# TOP.net
KiCad netlist of a schematic drawn in Altium Designer
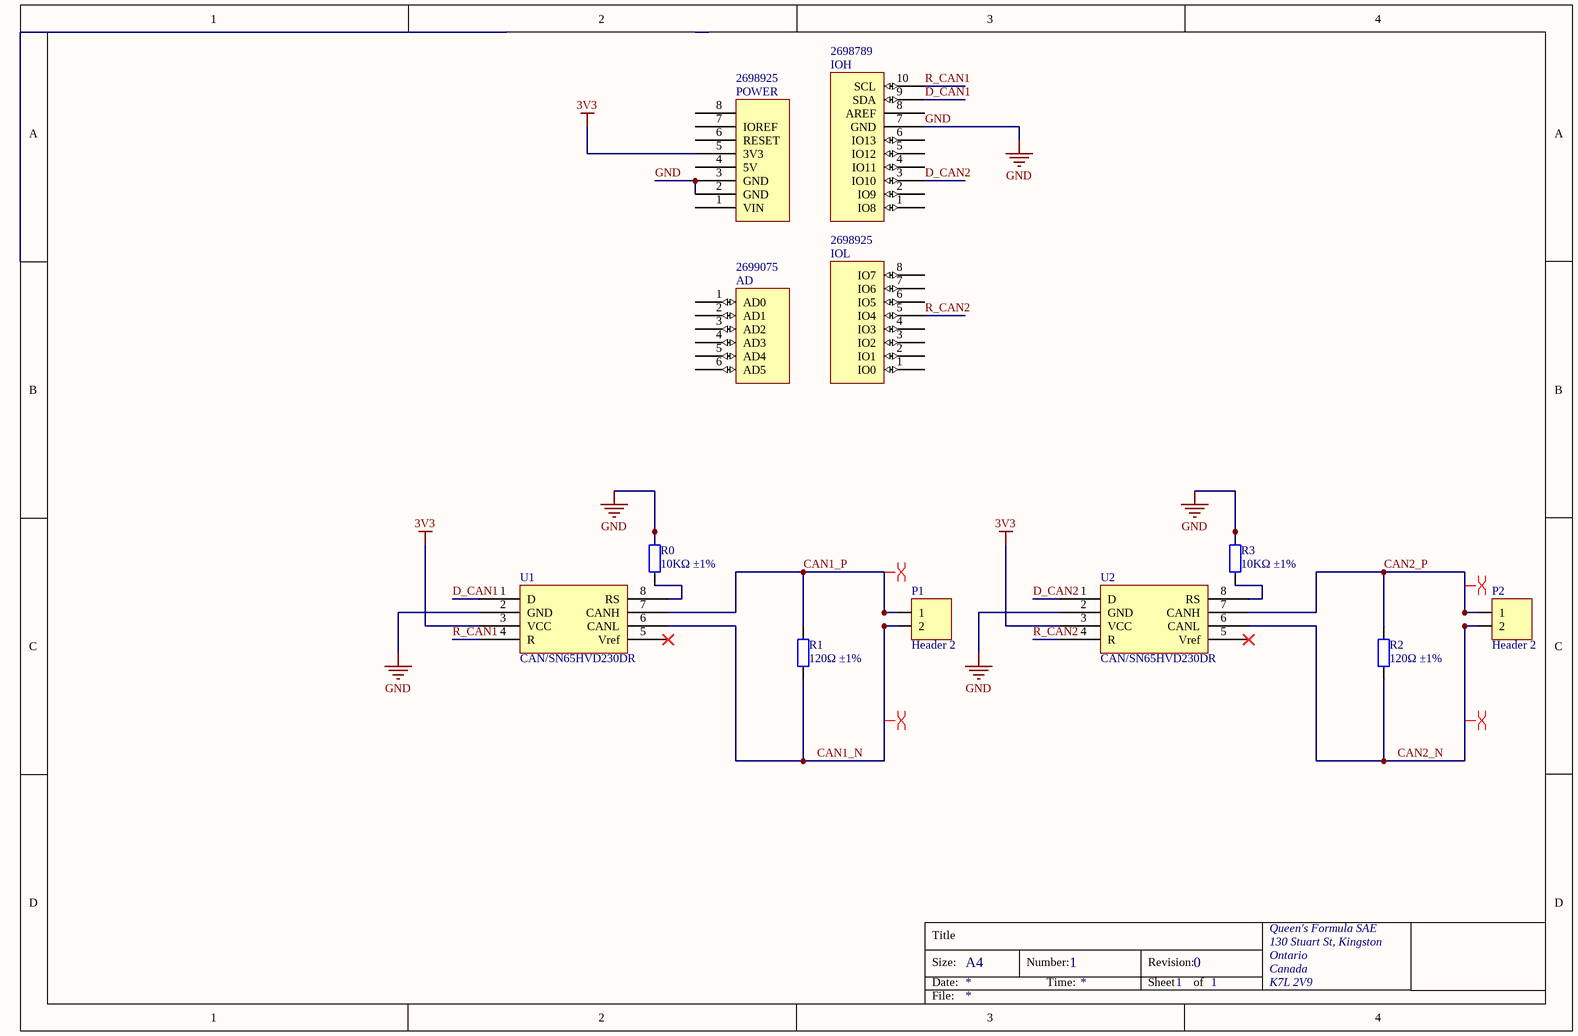
[diagram p0: TOP.SchDoc]

(export (version "E")
  (design (tool "Eeschema 10.0.6"))
  (components
    (comp (ref "AD")
      (value "AD")
      (footprint "Header:Header 6x1 8.5mm")
      (fields (field (name "SUPPLIER PART NUMBER 4") "2699075"))
      (libsource (lib "Header") (part "AD"))
    )
    (comp (ref "IOH")
      (value "IOH")
      (footprint "Header:Header 10x1 8.5mm")
      (fields (field (name "SUPPLIER PART NUMBER 3") "2698789"))
      (libsource (lib "Header") (part "IOH"))
    )
    (comp (ref "IOL")
      (value "IOL")
      (footprint "Header 8x1 8.5mm")
      (fields (field (name "SUPPLIER PART NUMBER 4") "2698925"))
      (libsource (lib "Header") (part "IOL"))
    )
    (comp (ref "P1")
      (value "Header 2")
      (footprint "HDR1X2")
      (description "Header, 2-Pin")
      (fields (field (name "PUBLISHER") "Altium Limited"))
      (libsource (lib "Miscellaneous Connectors") (part "Header 2"))
    )
    (comp (ref "P2")
      (value "Header 2")
      (footprint "HDR1X2")
      (description "Header, 2-Pin")
      (fields (field (name "PUBLISHER") "Altium Limited"))
      (libsource (lib "Miscellaneous Connectors") (part "Header 2"))
    )
    (comp (ref "POWER")
      (value "POWER_UNO")
      (footprint "Header 8x1 8.5mm")
      (fields (field (name "SUPPLIER PART NUMBER 4") "2698925"))
      (libsource (lib "Header") (part "POWER_UNO"))
    )
    (comp (ref "R0")
      (value "10KΩ ±1%")
      (footprint "0402_R")
      (description "Chip resistor")
      (fields (field (name "MANUFACTURER") "Uniroyal Elec") (field (name "PARTNUMBER") "0402WGF1002TCE"))
      (libsource (lib "RES") (part "0402 10K (1002) 1%"))
    )
    (comp (ref "R1")
      (value "120Ω ±1%")
      (footprint "0805_R")
      (description "Chip resistor")
      (fields (field (name "MANUFACTURER") "Uniroyal Elec") (field (name "POWER") "1/8W"))
      (libsource (lib "RES") (part "0805 120R (1200) 1%"))
    )
    (comp (ref "R2")
      (value "120Ω ±1%")
      (footprint "0805_R")
      (description "Chip resistor")
      (fields (field (name "MANUFACTURER") "Uniroyal Elec") (field (name "POWER") "1/8W"))
      (libsource (lib "RES") (part "0805 120R (1200) 1%"))
    )
    (comp (ref "R3")
      (value "10KΩ ±1%")
      (footprint "0402_R")
      (description "Chip resistor")
      (fields (field (name "MANUFACTURER") "Uniroyal Elec") (field (name "PARTNUMBER") "0402WGF1002TCE"))
      (libsource (lib "RES") (part "0402 10K (1002) 1%"))
    )
    (comp (ref "U1")
      (value "CAN/SN65HVD230DR")
      (footprint "SOIC-8_150mil")
      (description "CAN")
      (libsource (lib "IC") (part "CAN/SN65HVD230DR_[C12084]"))
    )
    (comp (ref "U2")
      (value "CAN/SN65HVD230DR")
      (footprint "SOIC-8_150mil")
      (description "CAN")
      (libsource (lib "IC") (part "CAN/SN65HVD230DR_[C12084]"))
    )
  )
  (nets
    (net (code "1") (name "/CAN1_N") (class "Default")
      (node (ref "P1") (pin "2") (pinfunction "2_2") (pintype "passive"))
      (node (ref "R1") (pin "2") (pinfunction "2_2") (pintype "passive"))
      (node (ref "U1") (pin "6") (pinfunction "CANL_6") (pintype "passive"))
    )
    (net (code "2") (name "/CAN1_P") (class "Default")
      (node (ref "P1") (pin "1") (pinfunction "1_1") (pintype "passive"))
      (node (ref "R1") (pin "1") (pinfunction "1_1") (pintype "passive"))
      (node (ref "U1") (pin "7") (pinfunction "CANH_7") (pintype "passive"))
    )
    (net (code "3") (name "/CAN2_N") (class "Default")
      (node (ref "P2") (pin "2") (pinfunction "2_2") (pintype "passive"))
      (node (ref "R2") (pin "2") (pinfunction "2_2") (pintype "passive"))
      (node (ref "U2") (pin "6") (pinfunction "CANL_6") (pintype "passive"))
    )
    (net (code "4") (name "/CAN2_P") (class "Default")
      (node (ref "P2") (pin "1") (pinfunction "1_1") (pintype "passive"))
      (node (ref "R2") (pin "1") (pinfunction "1_1") (pintype "passive"))
      (node (ref "U2") (pin "7") (pinfunction "CANH_7") (pintype "passive"))
    )
    (net (code "5") (name "/D_CAN1") (class "Default")
      (node (ref "IOH") (pin "9") (pinfunction "SDA_9") (pintype "bidirectional"))
      (node (ref "U1") (pin "1") (pinfunction "D_1") (pintype "passive"))
    )
    (net (code "6") (name "/D_CAN2") (class "Default")
      (node (ref "IOH") (pin "3") (pinfunction "IO10_3") (pintype "bidirectional"))
      (node (ref "U2") (pin "1") (pinfunction "D_1") (pintype "passive"))
    )
    (net (code "7") (name "/R_CAN1") (class "Default")
      (node (ref "IOH") (pin "10") (pinfunction "SCL_10") (pintype "bidirectional"))
      (node (ref "U1") (pin "4") (pinfunction "R_4") (pintype "passive"))
    )
    (net (code "8") (name "/R_CAN2") (class "Default")
      (node (ref "IOL") (pin "5") (pinfunction "IO4_5") (pintype "bidirectional"))
      (node (ref "U2") (pin "4") (pinfunction "R_4") (pintype "passive"))
    )
    (net (code "9") (name "3V3") (class "Default")
      (node (ref "POWER") (pin "5") (pinfunction "3V3_5") (pintype "power_in"))
      (node (ref "U1") (pin "3") (pinfunction "VCC_3") (pintype "passive"))
      (node (ref "U2") (pin "3") (pinfunction "VCC_3") (pintype "passive"))
    )
    (net (code "10") (name "GND") (class "Default")
      (node (ref "IOH") (pin "7") (pinfunction "GND_7") (pintype "power_in"))
      (node (ref "POWER") (pin "2") (pinfunction "GND_2") (pintype "power_in"))
      (node (ref "POWER") (pin "3") (pinfunction "GND_3") (pintype "power_in"))
      (node (ref "R0") (pin "2") (pinfunction "2_2") (pintype "passive"))
      (node (ref "R3") (pin "2") (pinfunction "2_2") (pintype "passive"))
      (node (ref "U1") (pin "2") (pinfunction "GND_2") (pintype "passive"))
      (node (ref "U2") (pin "2") (pinfunction "GND_2") (pintype "passive"))
    )
    (net (code "11") (name "Net-(U1-RS)") (class "Default")
      (node (ref "R0") (pin "1") (pinfunction "1_1") (pintype "passive"))
      (node (ref "U1") (pin "8") (pinfunction "RS_8") (pintype "passive"))
    )
    (net (code "12") (name "Net-(U2-RS)") (class "Default")
      (node (ref "R3") (pin "1") (pinfunction "1_1") (pintype "passive"))
      (node (ref "U2") (pin "8") (pinfunction "RS_8") (pintype "passive"))
    )
    (net (code "13") (name "unconnected-(AD-AD0-Pad1)") (class "Default")
      (node (ref "AD") (pin "1") (pinfunction "AD0_1") (pintype "bidirectional"))
    )
    (net (code "14") (name "unconnected-(AD-AD1-Pad2)") (class "Default")
      (node (ref "AD") (pin "2") (pinfunction "AD1_2") (pintype "bidirectional"))
    )
    (net (code "15") (name "unconnected-(AD-AD2-Pad3)") (class "Default")
      (node (ref "AD") (pin "3") (pinfunction "AD2_3") (pintype "bidirectional"))
    )
    (net (code "16") (name "unconnected-(AD-AD3-Pad4)") (class "Default")
      (node (ref "AD") (pin "4") (pinfunction "AD3_4") (pintype "bidirectional"))
    )
    (net (code "17") (name "unconnected-(AD-AD4-Pad5)") (class "Default")
      (node (ref "AD") (pin "5") (pinfunction "AD4_5") (pintype "bidirectional"))
    )
    (net (code "18") (name "unconnected-(AD-AD5-Pad6)") (class "Default")
      (node (ref "AD") (pin "6") (pinfunction "AD5_6") (pintype "bidirectional"))
    )
    (net (code "19") (name "unconnected-(IOH-AREF-Pad8)") (class "Default")
      (node (ref "IOH") (pin "8") (pinfunction "AREF_8") (pintype "passive"))
    )
    (net (code "20") (name "unconnected-(IOH-IO8-Pad1)") (class "Default")
      (node (ref "IOH") (pin "1") (pinfunction "IO8_1") (pintype "bidirectional"))
    )
    (net (code "21") (name "unconnected-(IOH-IO9-Pad2)") (class "Default")
      (node (ref "IOH") (pin "2") (pinfunction "IO9_2") (pintype "bidirectional"))
    )
    (net (code "22") (name "unconnected-(IOH-IO11-Pad4)") (class "Default")
      (node (ref "IOH") (pin "4") (pinfunction "IO11_4") (pintype "bidirectional"))
    )
    (net (code "23") (name "unconnected-(IOH-IO12-Pad5)") (class "Default")
      (node (ref "IOH") (pin "5") (pinfunction "IO12_5") (pintype "bidirectional"))
    )
    (net (code "24") (name "unconnected-(IOH-IO13-Pad6)") (class "Default")
      (node (ref "IOH") (pin "6") (pinfunction "IO13_6") (pintype "bidirectional"))
    )
    (net (code "25") (name "unconnected-(IOL-IO0-Pad1)") (class "Default")
      (node (ref "IOL") (pin "1") (pinfunction "IO0_1") (pintype "bidirectional"))
    )
    (net (code "26") (name "unconnected-(IOL-IO1-Pad2)") (class "Default")
      (node (ref "IOL") (pin "2") (pinfunction "IO1_2") (pintype "bidirectional"))
    )
    (net (code "27") (name "unconnected-(IOL-IO2-Pad3)") (class "Default")
      (node (ref "IOL") (pin "3") (pinfunction "IO2_3") (pintype "bidirectional"))
    )
    (net (code "28") (name "unconnected-(IOL-IO3-Pad4)") (class "Default")
      (node (ref "IOL") (pin "4") (pinfunction "IO3_4") (pintype "bidirectional"))
    )
    (net (code "29") (name "unconnected-(IOL-IO5-Pad6)") (class "Default")
      (node (ref "IOL") (pin "6") (pinfunction "IO5_6") (pintype "bidirectional"))
    )
    (net (code "30") (name "unconnected-(IOL-IO6-Pad7)") (class "Default")
      (node (ref "IOL") (pin "7") (pinfunction "IO6_7") (pintype "bidirectional"))
    )
    (net (code "31") (name "unconnected-(IOL-IO7-Pad8)") (class "Default")
      (node (ref "IOL") (pin "8") (pinfunction "IO7_8") (pintype "bidirectional"))
    )
    (net (code "32") (name "unconnected-(POWER-5V-Pad4)") (class "Default")
      (node (ref "POWER") (pin "4") (pinfunction "5V_4") (pintype "power_in"))
    )
    (net (code "33") (name "unconnected-(POWER-IOREF-Pad7)") (class "Default")
      (node (ref "POWER") (pin "7") (pinfunction "IOREF_7") (pintype "power_in"))
    )
    (net (code "34") (name "unconnected-(POWER-Pad8)") (class "Default")
      (node (ref "POWER") (pin "8") (pintype "passive"))
    )
    (net (code "35") (name "unconnected-(POWER-RESET-Pad6)") (class "Default")
      (node (ref "POWER") (pin "6") (pinfunction "RESET_6") (pintype "passive"))
    )
    (net (code "36") (name "unconnected-(POWER-VIN-Pad1)") (class "Default")
      (node (ref "POWER") (pin "1") (pinfunction "VIN_1") (pintype "power_in"))
    )
    (net (code "37") (name "unconnected-(U1-Vref-Pad5)") (class "Default")
      (node (ref "U1") (pin "5") (pinfunction "Vref_5") (pintype "passive+no_connect"))
    )
    (net (code "38") (name "unconnected-(U2-Vref-Pad5)") (class "Default")
      (node (ref "U2") (pin "5") (pinfunction "Vref_5") (pintype "passive+no_connect"))
    )
  )
)
